# ODGIRON-v1_0-F103-0413.net
KiCad netlist of a schematic drawn in EAGLE
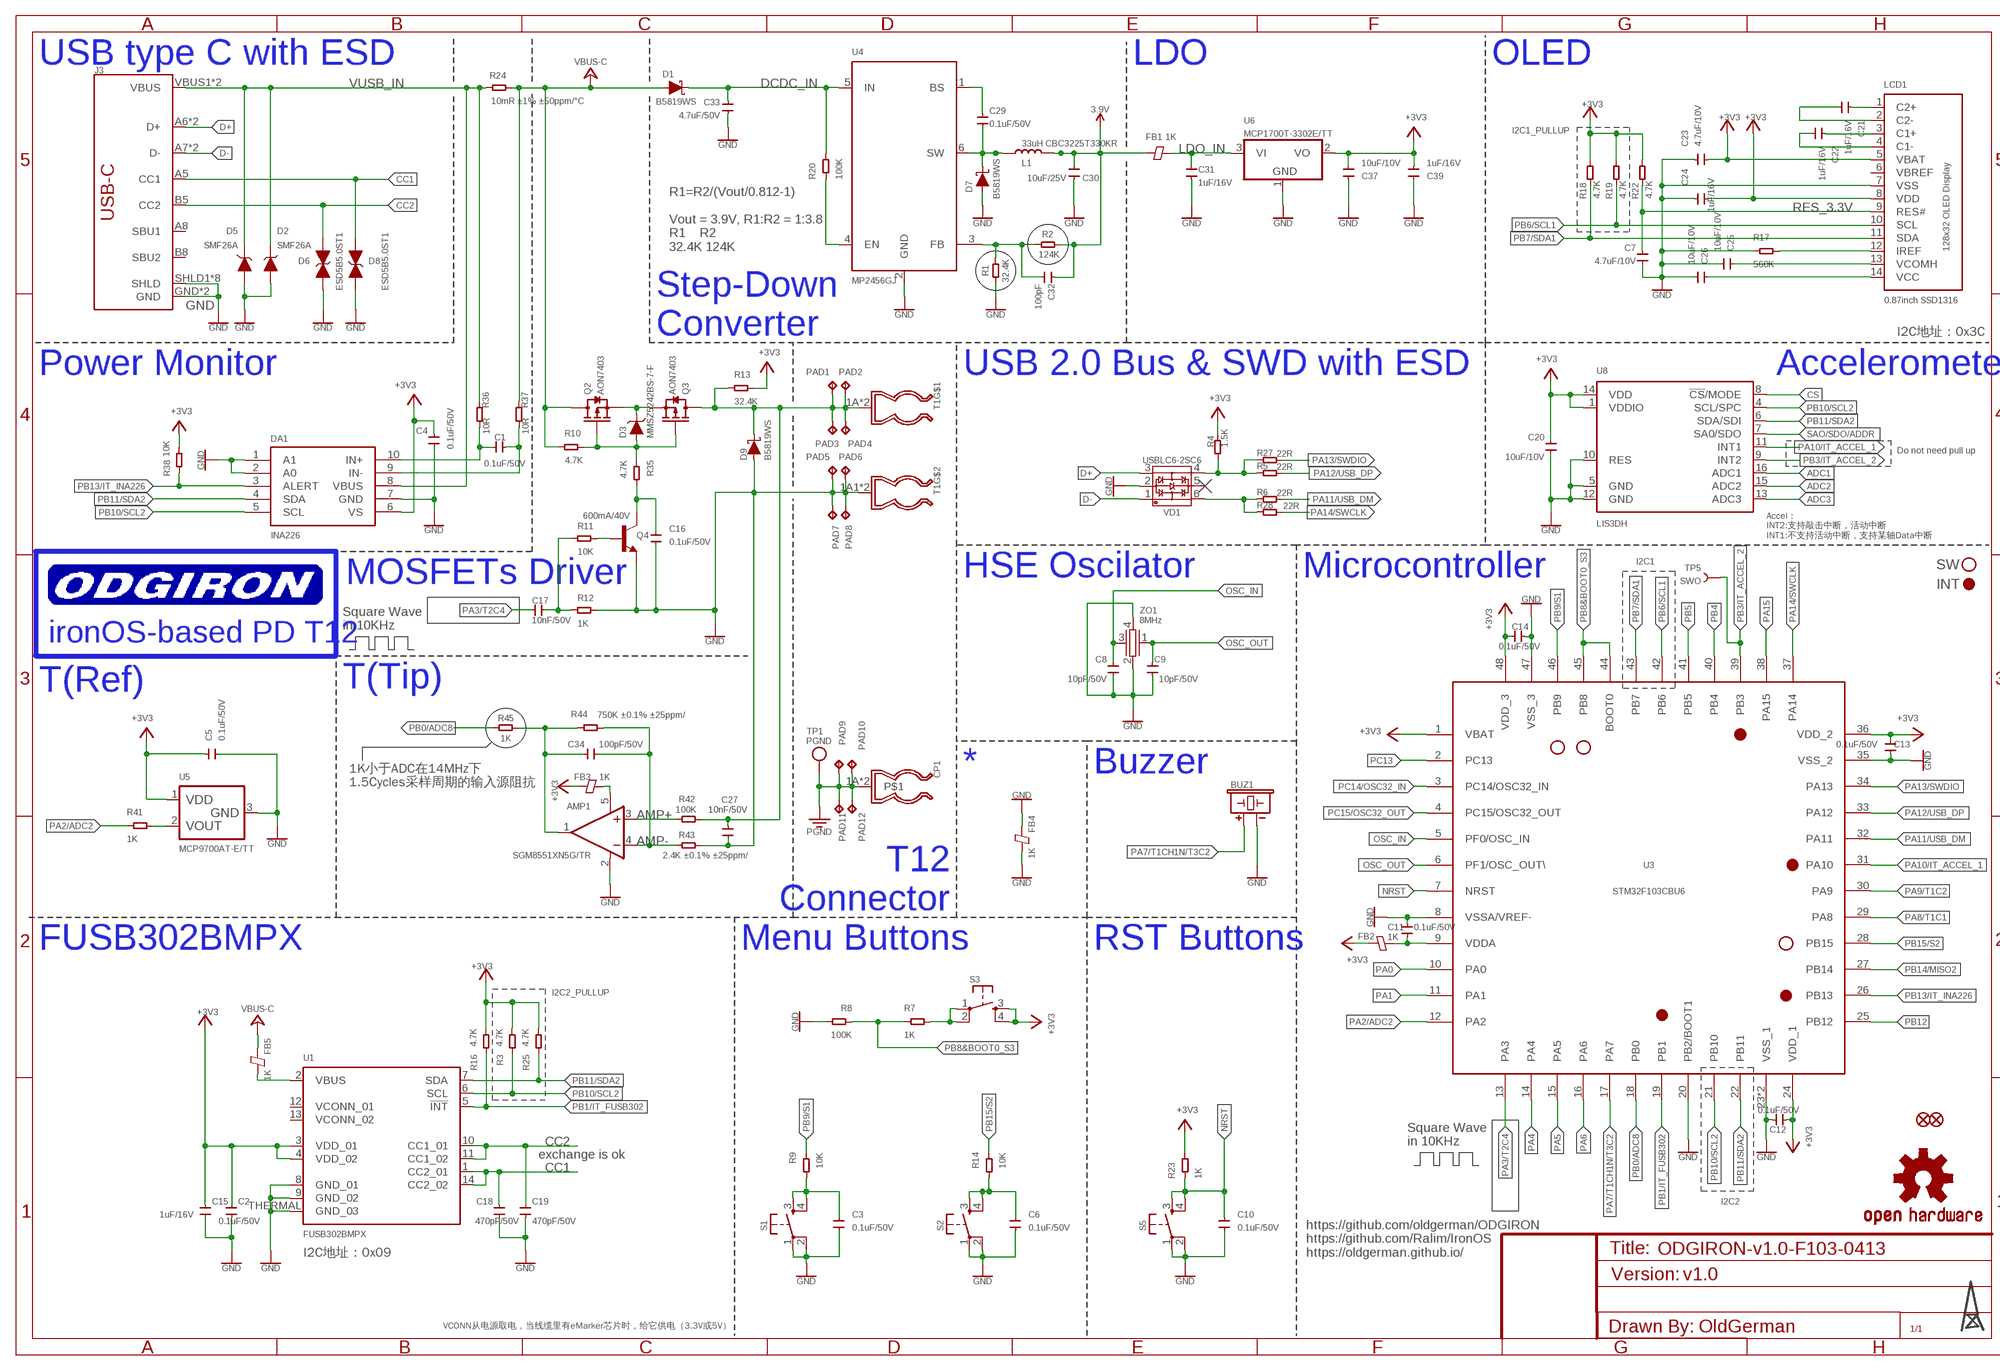
[diagram p0: schematic, sheet 1, part 1 of 2]
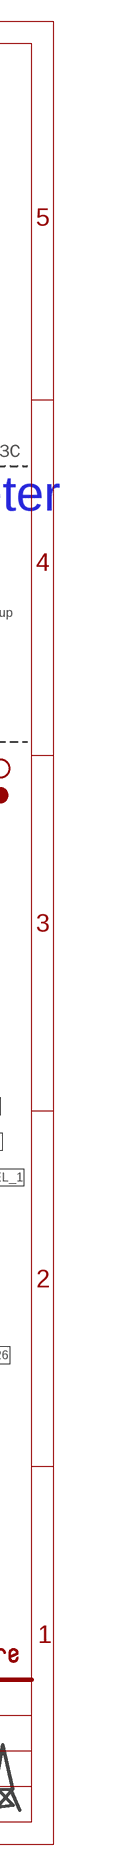
[diagram p1: schematic, sheet 1, part 2 of 2]

(export (version "E")
  (design (tool "Eeschema 10.0.6"))
  (components
    (comp (ref "AMP1")
      (value "SGM8551XN5G/TR")
      (footprint "eagle-import:SOT23-5")
      (fields (field (name "MPN") "OPA340NA/3KG4"))
      (libsource (lib "eagle-import") (part "AMP_SIMGLEN"))
    )
    (comp (ref "BUZ1")
      (value "BUZZERBUZZER_5020")
      (footprint "eagle-import:BUZZER_5020")
      (libsource (lib "eagle-import") (part "BUZZERBUZZER_5020"))
    )
    (comp (ref "C1")
      (value "0.1uF/50V")
      (footprint "eagle-import:C0603")
      (libsource (lib "eagle-import") (part "SEEED_CAP-0603"))
    )
    (comp (ref "C2")
      (value "0.1uF/50V")
      (footprint "eagle-import:C0603")
      (libsource (lib "eagle-import") (part "SEEED_CAP-0603"))
    )
    (comp (ref "C3")
      (value "0.1uF/50V")
      (footprint "eagle-import:C0603")
      (libsource (lib "eagle-import") (part "SEEED_CAP-0603"))
    )
    (comp (ref "C4")
      (value "0.1uF/50V")
      (footprint "eagle-import:C0603")
      (libsource (lib "eagle-import") (part "SEEED_CAP-0603"))
    )
    (comp (ref "C5")
      (value "0.1uF/50V")
      (footprint "eagle-import:C0603")
      (libsource (lib "eagle-import") (part "SEEED_CAP-0603"))
    )
    (comp (ref "C6")
      (value "0.1uF/50V")
      (footprint "eagle-import:C0603")
      (libsource (lib "eagle-import") (part "SEEED_CAP-0603"))
    )
    (comp (ref "C7")
      (value "4.7uF/10V")
      (footprint "eagle-import:C0603")
      (libsource (lib "eagle-import") (part "SEEED_CAP-0603"))
    )
    (comp (ref "C8")
      (value "10pF/50V")
      (footprint "eagle-import:C0603")
      (libsource (lib "eagle-import") (part "SEEED_CAP-0603"))
    )
    (comp (ref "C9")
      (value "10pF/50V")
      (footprint "eagle-import:C0603")
      (libsource (lib "eagle-import") (part "SEEED_CAP-0603"))
    )
    (comp (ref "C10")
      (value "0.1uF/50V")
      (footprint "eagle-import:C0603")
      (libsource (lib "eagle-import") (part "SEEED_CAP-0603"))
    )
    (comp (ref "C11")
      (value "0.1uF/50V")
      (footprint "eagle-import:C0603")
      (libsource (lib "eagle-import") (part "SEEED_CAP-0603"))
    )
    (comp (ref "C12")
      (value "0.1uF/50V")
      (footprint "eagle-import:C0603")
      (libsource (lib "eagle-import") (part "SEEED_CAP-0603"))
    )
    (comp (ref "C13")
      (value "0.1uF/50V")
      (footprint "eagle-import:C0603")
      (libsource (lib "eagle-import") (part "SEEED_CAP-0603"))
    )
    (comp (ref "C14")
      (value "0.1uF/50V")
      (footprint "eagle-import:C0603")
      (libsource (lib "eagle-import") (part "SEEED_CAP-0603"))
    )
    (comp (ref "C15")
      (value "1uF/16V")
      (footprint "eagle-import:C0603")
      (libsource (lib "eagle-import") (part "SEEED_CAP-0603"))
    )
    (comp (ref "C16")
      (value "0.1uF/50V")
      (footprint "eagle-import:C0603")
      (libsource (lib "eagle-import") (part "SEEED_CAP-0603"))
    )
    (comp (ref "C17")
      (value "10nF/50V")
      (footprint "eagle-import:C0603")
      (libsource (lib "eagle-import") (part "SEEED_CAP-0603"))
    )
    (comp (ref "C18")
      (value "470pF/50V")
      (footprint "eagle-import:C0603")
      (libsource (lib "eagle-import") (part "SEEED_CAP-0603"))
    )
    (comp (ref "C19")
      (value "470pF/50V")
      (footprint "eagle-import:C0603")
      (libsource (lib "eagle-import") (part "SEEED_CAP-0603"))
    )
    (comp (ref "C20")
      (value "10uF/10V")
      (footprint "eagle-import:C0603")
      (libsource (lib "eagle-import") (part "SEEED_CAP-0603"))
    )
    (comp (ref "C21")
      (value "1uF/16V")
      (footprint "eagle-import:C0603")
      (libsource (lib "eagle-import") (part "SEEED_CAP-0603"))
    )
    (comp (ref "C22")
      (value "1uF/16V")
      (footprint "eagle-import:C0603")
      (libsource (lib "eagle-import") (part "SEEED_CAP-0603"))
    )
    (comp (ref "C23")
      (value "4.7uF/10V")
      (footprint "eagle-import:C0603")
      (libsource (lib "eagle-import") (part "SEEED_CAP-0603"))
    )
    (comp (ref "C24")
      (value "1uF/16V")
      (footprint "eagle-import:C0603")
      (libsource (lib "eagle-import") (part "SEEED_CAP-0603"))
    )
    (comp (ref "C25")
      (value "10uF/10V")
      (footprint "eagle-import:C0603")
      (libsource (lib "eagle-import") (part "SEEED_CAP-0603"))
    )
    (comp (ref "C26")
      (value "10uF/10V")
      (footprint "eagle-import:C0603")
      (libsource (lib "eagle-import") (part "SEEED_CAP-0603"))
    )
    (comp (ref "C27")
      (value "10nF/50V")
      (footprint "eagle-import:C0603")
      (libsource (lib "eagle-import") (part "SEEED_CAP-0603"))
    )
    (comp (ref "C29")
      (value "0.1uF/50V")
      (footprint "eagle-import:C0603")
      (libsource (lib "eagle-import") (part "SEEED_CAP-0603"))
    )
    (comp (ref "C30")
      (value "10uF/25V")
      (footprint "eagle-import:C0805")
      (libsource (lib "eagle-import") (part "SEEED_CAP-0805"))
    )
    (comp (ref "C31")
      (value "1uF/16V")
      (footprint "eagle-import:C0603")
      (libsource (lib "eagle-import") (part "SEEED_CAP-0603"))
    )
    (comp (ref "C32")
      (value "100pF")
      (footprint "eagle-import:C0603")
      (libsource (lib "eagle-import") (part "SEEED_CAP-0603"))
    )
    (comp (ref "C33")
      (value "4.7uF/50V")
      (footprint "eagle-import:C0805")
      (libsource (lib "eagle-import") (part "SEEED_CAP-0805"))
    )
    (comp (ref "C34")
      (value "100pF/50V")
      (footprint "eagle-import:C0603")
      (libsource (lib "eagle-import") (part "SEEED_CAP-0603"))
    )
    (comp (ref "C37")
      (value "10uF/10V")
      (footprint "eagle-import:C0603")
      (libsource (lib "eagle-import") (part "SEEED_CAP-0603"))
    )
    (comp (ref "C39")
      (value "1uF/16V")
      (footprint "eagle-import:C0603")
      (libsource (lib "eagle-import") (part "SEEED_CAP-0603"))
    )
    (comp (ref "CP1")
      (value "FUSE_CLIPS_01")
      (footprint "eagle-import:FUSE_CLIPS_01")
      (libsource (lib "eagle-import") (part "FUSE_CLIPS_01"))
    )
    (comp (ref "D1")
      (value "B5819WS")
      (footprint "eagle-import:SOD-323")
      (libsource (lib "eagle-import") (part "DIODE_SCHOTTKYSOD323"))
    )
    (comp (ref "D2")
      (value "SMF26A")
      (footprint "eagle-import:SOD-123")
      (libsource (lib "eagle-import") (part "DIODE-TVS_UNIDIRECTIONALSOD-123"))
    )
    (comp (ref "D3")
      (value "MMSZ5242BS-7-F")
      (footprint "eagle-import:SOD-323")
      (libsource (lib "eagle-import") (part "DIODE_ZENERSOD-323"))
    )
    (comp (ref "D5")
      (value "SMF26A")
      (footprint "eagle-import:SOD-123")
      (libsource (lib "eagle-import") (part "DIODE-TVS_UNIDIRECTIONALSOD-123"))
    )
    (comp (ref "D6")
      (value "ESD5B5.0ST1")
      (footprint "eagle-import:SOD-523")
      (libsource (lib "eagle-import") (part "DIODE-TVS_BI−DIRECTIONALSOD-523"))
    )
    (comp (ref "D7")
      (value "B5819WS")
      (footprint "eagle-import:SOD-323")
      (libsource (lib "eagle-import") (part "DIODE_SCHOTTKYSOD323"))
    )
    (comp (ref "D8")
      (value "ESD5B5.0ST1")
      (footprint "eagle-import:SOD-523")
      (libsource (lib "eagle-import") (part "DIODE-TVS_BI−DIRECTIONALSOD-523"))
    )
    (comp (ref "D9")
      (value "B5819WS")
      (footprint "eagle-import:SOD-323")
      (libsource (lib "eagle-import") (part "DIODE_SCHOTTKYSOD323"))
    )
    (comp (ref "DA1")
      (value "INA226")
      (footprint "eagle-import:MSOP10")
      (libsource (lib "eagle-import") (part "INA226"))
    )
    (comp (ref "FB1")
      (value "1K")
      (footprint "eagle-import:F0603")
      (libsource (lib "eagle-import") (part "FERRITE-BEAD-0603"))
    )
    (comp (ref "FB2")
      (value "1K")
      (footprint "eagle-import:F0603")
      (libsource (lib "eagle-import") (part "FERRITE-BEAD-0603"))
    )
    (comp (ref "FB3")
      (value "1K")
      (footprint "eagle-import:F0603")
      (libsource (lib "eagle-import") (part "FERRITE-BEAD-0603"))
    )
    (comp (ref "FB4")
      (value "1K")
      (footprint "eagle-import:F0603")
      (libsource (lib "eagle-import") (part "FERRITE-BEAD-0603"))
    )
    (comp (ref "FB5")
      (value "1K")
      (footprint "eagle-import:F0603")
      (libsource (lib "eagle-import") (part "FERRITE-BEAD-0603"))
    )
    (comp (ref "FID1")
      (value "FIDUCIAL")
      (footprint "eagle-import:FIDUCIAL_1MM")
      (libsource (lib "eagle-import") (part "FIDUCIAL"))
    )
    (comp (ref "FID2")
      (value "FIDUCIAL")
      (footprint "eagle-import:FIDUCIAL_1MM")
      (libsource (lib "eagle-import") (part "FIDUCIAL"))
    )
    (comp (ref "J3")
      (value "USB_C_LONG-SYMBOL2-LAYER")
      (footprint "eagle-import:USB-C-16P")
      (libsource (lib "eagle-import") (part "USB_C_LONG-SYMBOL2-LAYER"))
    )
    (comp (ref "L1")
      (value "33uH CBC3225T330KR")
      (footprint "eagle-import:SMD,3.2X2.5X2.5MM")
      (libsource (lib "eagle-import") (part "INDUCTOR3225"))
    )
    (comp (ref "LCD1")
      (value "0.87inch SSD1316")
      (footprint "eagle-import:0.87INCH_128X32_OLED_SSD1306")
      (libsource (lib "eagle-import") (part "0.87INCH_OLED_128X32_SSD1306"))
    )
    (comp (ref "LOGO1")
      (value "OSHW-LOGONO_SILK")
      (footprint "eagle-import:DUMMY")
      (libsource (lib "eagle-import") (part "OSHW-LOGONO_SILK"))
    )
    (comp (ref "PAD1")
      (value "PADTP16SQ")
      (footprint "eagle-import:TP16SQ")
      (libsource (lib "eagle-import") (part "PADTP16SQ"))
    )
    (comp (ref "PAD2")
      (value "PADTP16SQ")
      (footprint "eagle-import:TP16SQ")
      (libsource (lib "eagle-import") (part "PADTP16SQ"))
    )
    (comp (ref "PAD3")
      (value "PADTP16SQ")
      (footprint "eagle-import:TP16SQ")
      (libsource (lib "eagle-import") (part "PADTP16SQ"))
    )
    (comp (ref "PAD4")
      (value "PADTP16SQ")
      (footprint "eagle-import:TP16SQ")
      (libsource (lib "eagle-import") (part "PADTP16SQ"))
    )
    (comp (ref "PAD5")
      (value "PADTP16SQ")
      (footprint "eagle-import:TP16SQ")
      (libsource (lib "eagle-import") (part "PADTP16SQ"))
    )
    (comp (ref "PAD6")
      (value "PADTP16SQ")
      (footprint "eagle-import:TP16SQ")
      (libsource (lib "eagle-import") (part "PADTP16SQ"))
    )
    (comp (ref "PAD7")
      (value "PADTP16SQ")
      (footprint "eagle-import:TP16SQ")
      (libsource (lib "eagle-import") (part "PADTP16SQ"))
    )
    (comp (ref "PAD8")
      (value "PADTP16SQ")
      (footprint "eagle-import:TP16SQ")
      (libsource (lib "eagle-import") (part "PADTP16SQ"))
    )
    (comp (ref "PAD9")
      (value "PADTP16SQ")
      (footprint "eagle-import:TP16SQ")
      (libsource (lib "eagle-import") (part "PADTP16SQ"))
    )
    (comp (ref "PAD10")
      (value "PADTP16SQ")
      (footprint "eagle-import:TP16SQ")
      (libsource (lib "eagle-import") (part "PADTP16SQ"))
    )
    (comp (ref "PAD11")
      (value "PADTP16SQ")
      (footprint "eagle-import:TP16SQ")
      (libsource (lib "eagle-import") (part "PADTP16SQ"))
    )
    (comp (ref "PAD12")
      (value "PADTP16SQ")
      (footprint "eagle-import:TP16SQ")
      (libsource (lib "eagle-import") (part "PADTP16SQ"))
    )
    (comp (ref "Q2")
      (value "AON7403")
      (footprint "eagle-import:DFN8P-0.65-3X3X0.8MM")
      (libsource (lib "eagle-import") (part "MOSFET-P-AON7403"))
    )
    (comp (ref "Q3")
      (value "AON7403")
      (footprint "eagle-import:DFN8P-0.65-3X3X0.8MM")
      (libsource (lib "eagle-import") (part "MOSFET-P-AON7403"))
    )
    (comp (ref "Q4")
      (value "600mA/40V")
      (footprint "eagle-import:SOT23-3")
      (libsource (lib "eagle-import") (part "TRANS_NPN-MMBT2222AL"))
    )
    (comp (ref "R1")
      (value "32.4K")
      (footprint "eagle-import:R0603")
      (libsource (lib "eagle-import") (part "SEEED_RES-0603"))
    )
    (comp (ref "R2")
      (value "124K")
      (footprint "eagle-import:R0603")
      (libsource (lib "eagle-import") (part "SEEED_RES-0603"))
    )
    (comp (ref "R3")
      (value "4.7K")
      (footprint "eagle-import:R0603")
      (libsource (lib "eagle-import") (part "SEEED_RES-0603"))
    )
    (comp (ref "R4")
      (value "1.5K")
      (footprint "eagle-import:R0603")
      (libsource (lib "eagle-import") (part "SEEED_RES-0603"))
    )
    (comp (ref "R5")
      (value "22R")
      (footprint "eagle-import:R0603")
      (libsource (lib "eagle-import") (part "SEEED_RES-0603"))
    )
    (comp (ref "R6")
      (value "22R")
      (footprint "eagle-import:R0603")
      (libsource (lib "eagle-import") (part "SEEED_RES-0603"))
    )
    (comp (ref "R7")
      (value "1K")
      (footprint "eagle-import:R0603")
      (libsource (lib "eagle-import") (part "SEEED_RES-0603"))
    )
    (comp (ref "R8")
      (value "100K")
      (footprint "eagle-import:R0603")
      (libsource (lib "eagle-import") (part "SEEED_RES-0603"))
    )
    (comp (ref "R9")
      (value "10K")
      (footprint "eagle-import:R0603")
      (libsource (lib "eagle-import") (part "SEEED_RES-0603"))
    )
    (comp (ref "R10")
      (value "4.7K")
      (footprint "eagle-import:R0603")
      (libsource (lib "eagle-import") (part "SEEED_RES-0603"))
    )
    (comp (ref "R11")
      (value "10K")
      (footprint "eagle-import:R0603")
      (libsource (lib "eagle-import") (part "SEEED_RES-0603"))
    )
    (comp (ref "R12")
      (value "1K")
      (footprint "eagle-import:R0603")
      (libsource (lib "eagle-import") (part "SEEED_RES-0603"))
    )
    (comp (ref "R13")
      (value "32.4K")
      (footprint "eagle-import:R0603")
      (libsource (lib "eagle-import") (part "SEEED_RES-0603"))
    )
    (comp (ref "R14")
      (value "10K")
      (footprint "eagle-import:R0603")
      (libsource (lib "eagle-import") (part "SEEED_RES-0603"))
    )
    (comp (ref "R16")
      (value "4.7K")
      (footprint "eagle-import:R0603")
      (libsource (lib "eagle-import") (part "SEEED_RES-0603"))
    )
    (comp (ref "R17")
      (value "560K")
      (footprint "eagle-import:R0603")
      (libsource (lib "eagle-import") (part "SEEED_RES-0603"))
    )
    (comp (ref "R18")
      (value "4.7K")
      (footprint "eagle-import:R0603")
      (libsource (lib "eagle-import") (part "SEEED_RES-0603"))
    )
    (comp (ref "R19")
      (value "4.7K")
      (footprint "eagle-import:R0603")
      (libsource (lib "eagle-import") (part "SEEED_RES-0603"))
    )
    (comp (ref "R20")
      (value "100K")
      (footprint "eagle-import:R0603")
      (libsource (lib "eagle-import") (part "SEEED_RES-0603"))
    )
    (comp (ref "R22")
      (value "4.7K")
      (footprint "eagle-import:R0603")
      (libsource (lib "eagle-import") (part "SEEED_RES-0603"))
    )
    (comp (ref "R23")
      (value "1K")
      (footprint "eagle-import:R0603")
      (libsource (lib "eagle-import") (part "SEEED_RES-0603"))
    )
    (comp (ref "R24")
      (value "10mR ±1% ±50ppm/°C")
      (footprint "eagle-import:R1206")
      (libsource (lib "eagle-import") (part "SEEED_RES-1206"))
    )
    (comp (ref "R25")
      (value "4.7K")
      (footprint "eagle-import:R0603")
      (libsource (lib "eagle-import") (part "SEEED_RES-0603"))
    )
    (comp (ref "R27")
      (value "22R")
      (footprint "eagle-import:R0603")
      (libsource (lib "eagle-import") (part "SEEED_RES-0603"))
    )
    (comp (ref "R28")
      (value "22R")
      (footprint "eagle-import:R0603")
      (libsource (lib "eagle-import") (part "SEEED_RES-0603"))
    )
    (comp (ref "R35")
      (value "4.7K")
      (footprint "eagle-import:R0603")
      (libsource (lib "eagle-import") (part "SEEED_RES-0603"))
    )
    (comp (ref "R36")
      (value "10R")
      (footprint "eagle-import:R0603")
      (libsource (lib "eagle-import") (part "SEEED_RES-0603"))
    )
    (comp (ref "R37")
      (value "10R")
      (footprint "eagle-import:R0603")
      (libsource (lib "eagle-import") (part "SEEED_RES-0603"))
    )
    (comp (ref "R38")
      (value "10K")
      (footprint "eagle-import:R0603")
      (libsource (lib "eagle-import") (part "SEEED_RES-0603"))
    )
    (comp (ref "R41")
      (value "1K")
      (footprint "eagle-import:R0603")
      (libsource (lib "eagle-import") (part "SEEED_RES-0603"))
    )
    (comp (ref "R42")
      (value "100K")
      (footprint "eagle-import:R0603")
      (libsource (lib "eagle-import") (part "SEEED_RES-0603"))
    )
    (comp (ref "R43")
      (value "2.4K ±0.1% ±25ppm/℃")
      (footprint "eagle-import:R0603")
      (libsource (lib "eagle-import") (part "SEEED_RES-0603"))
    )
    (comp (ref "R44")
      (value "750K ±0.1% ±25ppm/℃")
      (footprint "eagle-import:R0603")
      (libsource (lib "eagle-import") (part "SEEED_RES-0603"))
    )
    (comp (ref "R45")
      (value "1K")
      (footprint "eagle-import:R0603")
      (libsource (lib "eagle-import") (part "SEEED_RES-0603"))
    )
    (comp (ref "S1")
      (value "TAC_SWITCHSMD")
      (footprint "eagle-import:TACTILE_SWITCH_SMD")
      (libsource (lib "eagle-import") (part "TAC_SWITCHSMD"))
    )
    (comp (ref "S2")
      (value "TAC_SWITCHSMD")
      (footprint "eagle-import:TACTILE_SWITCH_SMD")
      (libsource (lib "eagle-import") (part "TAC_SWITCHSMD"))
    )
    (comp (ref "S3")
      (value "TAC_SWITCHSMD")
      (footprint "eagle-import:TACTILE_SWITCH_SMD")
      (libsource (lib "eagle-import") (part "TAC_SWITCHSMD"))
    )
    (comp (ref "S5")
      (value "TAC_SWITCHSMD")
      (footprint "eagle-import:TACTILE_SWITCH_SMD")
      (libsource (lib "eagle-import") (part "untitled_TAC_SWITCHSMD"))
    )
    (comp (ref "T1")
      (value "HAKKO_T12_K-TYPE_WITH_FUSE_CLIPS_X2")
      (footprint "eagle-import:HAKKO_T12_K-TYPE_WITH_FUSE_CLIPS_X2")
      (libsource (lib "eagle-import") (part "HAKKO_T12_K-TYPE_WITH_FUSE_CLIPS_X2"))
    )
    (comp (ref "TP1")
      (value "PGND")
      (footprint "eagle-import:TESTPOINT_ROUND_2MM")
      (libsource (lib "eagle-import") (part "TESTPOINTROUND2MM"))
    )
    (comp (ref "TP5")
      (value "SWO")
      (footprint "eagle-import:PAD.03X.03")
      (libsource (lib "eagle-import") (part "TEST-POINT3"))
    )
    (comp (ref "U1")
      (value "FUSB302BMPX")
      (footprint "eagle-import:QFN14-2.5X2.5MM")
      (libsource (lib "eagle-import") (part "FUSB302"))
    )
    (comp (ref "U3")
      (value "STM32F103CBU6")
      (footprint "eagle-import:QFN48_7X7MM_0.5MM")
      (libsource (lib "eagle-import") (part "STM32F1_QFN48"))
    )
    (comp (ref "U4")
      (value "MP2456GJ")
      (footprint "eagle-import:SOT23-6")
      (libsource (lib "eagle-import") (part "MP2456"))
    )
    (comp (ref "U5")
      (value "MCP9700AT-E/TT")
      (footprint "eagle-import:SOT23-3@1")
      (libsource (lib "eagle-import") (part "MCP9700"))
    )
    (comp (ref "U6")
      (value "MCP1700T-3302E/TT")
      (footprint "eagle-import:SOT23-3")
      (libsource (lib "eagle-import") (part "MCP1700"))
    )
    (comp (ref "U8")
      (value "LIS3DH")
      (footprint "eagle-import:LGA-16-3X3")
      (libsource (lib "eagle-import") (part "LIS3DH"))
    )
    (comp (ref "VD1")
      (value "USBLC6-2SC6")
      (footprint "eagle-import:SOT23-6")
      (libsource (lib "eagle-import") (part "USBLC6-2SOT23-6"))
    )
    (comp (ref "ZO1")
      (value "8MHz")
      (footprint "eagle-import:3.2X2.5_KX-7")
      (libsource (lib "eagle-import") (part "3225_CRYSTALL"))
    )
  )
  (nets
    (net (code "1") (name "+3V3") (class "Default")
      (node (ref "C12") (pin "2") (pinfunction "P$2_2") (pintype "passive"))
      (node (ref "C13") (pin "2") (pinfunction "P$2_2") (pintype "passive"))
      (node (ref "C14") (pin "2") (pinfunction "P$2_2") (pintype "passive"))
      (node (ref "C15") (pin "1") (pinfunction "P$1_1") (pintype "passive"))
      (node (ref "C2") (pin "1") (pinfunction "P$1_1") (pintype "passive"))
      (node (ref "C20") (pin "2") (pinfunction "P$2_2") (pintype "passive"))
      (node (ref "C23") (pin "2") (pinfunction "P$2_2") (pintype "passive"))
      (node (ref "C24") (pin "2") (pinfunction "P$2_2") (pintype "passive"))
      (node (ref "C37") (pin "2") (pinfunction "P$2_2") (pintype "passive"))
      (node (ref "C39") (pin "2") (pinfunction "P$2_2") (pintype "passive"))
      (node (ref "C4") (pin "1") (pinfunction "P$1_1") (pintype "passive"))
      (node (ref "C5") (pin "1") (pinfunction "P$1_1") (pintype "passive"))
      (node (ref "DA1") (pin "6") (pinfunction "VS_6") (pintype "bidirectional"))
      (node (ref "FB2") (pin "2") (pinfunction "2_2") (pintype "bidirectional"))
      (node (ref "FB3") (pin "2") (pinfunction "2_2") (pintype "bidirectional"))
      (node (ref "LCD1") (pin "5") (pinfunction "VBAT_5") (pintype "power_in"))
      (node (ref "LCD1") (pin "8") (pinfunction "VDD_8") (pintype "power_in"))
      (node (ref "R13") (pin "2") (pinfunction "2_2") (pintype "passive"))
      (node (ref "R16") (pin "1") (pinfunction "1_1") (pintype "passive"))
      (node (ref "R18") (pin "2") (pinfunction "2_2") (pintype "passive"))
      (node (ref "R19") (pin "2") (pinfunction "2_2") (pintype "passive"))
      (node (ref "R22") (pin "2") (pinfunction "2_2") (pintype "passive"))
      (node (ref "R23") (pin "2") (pinfunction "2_2") (pintype "passive"))
      (node (ref "R25") (pin "1") (pinfunction "1_1") (pintype "passive"))
      (node (ref "R3") (pin "1") (pinfunction "1_1") (pintype "passive"))
      (node (ref "R38") (pin "1") (pinfunction "1_1") (pintype "passive"))
      (node (ref "R4") (pin "2") (pinfunction "2_2") (pintype "passive"))
      (node (ref "S3") (pin "3") (pinfunction "3_3") (pintype "passive"))
      (node (ref "S3") (pin "4") (pinfunction "4_4") (pintype "passive"))
      (node (ref "U1") (pin "3") (pinfunction "VDD_01_3") (pintype "bidirectional"))
      (node (ref "U1") (pin "4") (pinfunction "VDD_02_4") (pintype "bidirectional"))
      (node (ref "U3") (pin "1") (pinfunction "VBAT_1") (pintype "bidirectional"))
      (node (ref "U3") (pin "24") (pinfunction "VDD_1_24") (pintype "bidirectional"))
      (node (ref "U3") (pin "36") (pinfunction "VDD_2_36") (pintype "bidirectional"))
      (node (ref "U3") (pin "48") (pinfunction "VDD_3_48") (pintype "bidirectional"))
      (node (ref "U5") (pin "1") (pinfunction "VDD_1") (pintype "input"))
      (node (ref "U6") (pin "2") (pinfunction "VO_2") (pintype "passive"))
      (node (ref "U8") (pin "1") (pinfunction "VDDIO_1") (pintype "bidirectional"))
      (node (ref "U8") (pin "14") (pinfunction "VDD_14") (pintype "bidirectional"))
    )
    (net (code "2") (name "/AMP+") (class "Default")
      (node (ref "AMP1") (pin "3") (pinfunction "+IN_3") (pintype "input"))
      (node (ref "R42") (pin "1") (pinfunction "1_1") (pintype "passive"))
    )
    (net (code "3") (name "/AMP-") (class "Default")
      (node (ref "AMP1") (pin "4") (pinfunction "-IN_4") (pintype "input"))
      (node (ref "C34") (pin "2") (pinfunction "P$2_2") (pintype "passive"))
      (node (ref "R43") (pin "1") (pinfunction "1_1") (pintype "passive"))
      (node (ref "R44") (pin "2") (pinfunction "2_2") (pintype "passive"))
    )
    (net (code "4") (name "/DCDC_IN") (class "Default")
      (node (ref "C33") (pin "1") (pinfunction "P$1_1") (pintype "passive"))
      (node (ref "D1") (pin "C") (pinfunction "C_C") (pintype "passive"))
      (node (ref "R20") (pin "2") (pinfunction "2_2") (pintype "passive"))
      (node (ref "U4") (pin "5") (pinfunction "IN_5") (pintype "bidirectional"))
    )
    (net (code "5") (name "/LDO_IN") (class "Default")
      (node (ref "C31") (pin "2") (pinfunction "P$2_2") (pintype "passive"))
      (node (ref "FB1") (pin "2") (pinfunction "2_2") (pintype "bidirectional"))
      (node (ref "U6") (pin "3") (pinfunction "VI_3") (pintype "input"))
    )
    (net (code "6") (name "/RES_3.3V") (class "Default")
      (node (ref "C7") (pin "1") (pinfunction "P$1_1") (pintype "passive"))
      (node (ref "LCD1") (pin "9") (pinfunction "RES#_9") (pintype "bidirectional"))
      (node (ref "R22") (pin "1") (pinfunction "1_1") (pintype "passive"))
    )
    (net (code "7") (name "/VBREF") (class "Default")
      (node (ref "LCD1") (pin "6") (pinfunction "VBREF_6") (pintype "power_in"))
    )
    (net (code "8") (name "/VUSB_IN") (class "Default")
      (node (ref "D2") (pin "C") (pinfunction "K_C") (pintype "passive"))
      (node (ref "D5") (pin "C") (pinfunction "K_C") (pintype "passive"))
      (node (ref "DA1") (pin "8") (pinfunction "VBUS_8") (pintype "bidirectional"))
      (node (ref "J3") (pin "VBUS1") (pinfunction "VBUS_VBUS1") (pintype "bidirectional"))
      (node (ref "J3") (pin "VBUS2") (pinfunction "VBUS_VBUS2") (pintype "bidirectional"))
      (node (ref "R24") (pin "2") (pinfunction "2_2") (pintype "passive"))
      (node (ref "R36") (pin "2") (pinfunction "2_2") (pintype "passive"))
    )
    (net (code "9") (name "3.9V") (class "Default")
      (node (ref "C30") (pin "1") (pinfunction "P$1_1") (pintype "passive"))
      (node (ref "C32") (pin "1") (pinfunction "P$1_1") (pintype "passive"))
      (node (ref "FB1") (pin "1") (pinfunction "1_1") (pintype "bidirectional"))
      (node (ref "L1") (pin "2") (pinfunction "2_2") (pintype "passive"))
      (node (ref "R2") (pin "1") (pinfunction "1_1") (pintype "passive"))
    )
    (net (code "10") (name "ADC1") (class "Default")
      (node (ref "U8") (pin "16") (pinfunction "ADC1_16") (pintype "bidirectional"))
    )
    (net (code "11") (name "ADC2") (class "Default")
      (node (ref "U8") (pin "15") (pinfunction "ADC2_15") (pintype "bidirectional"))
    )
    (net (code "12") (name "ADC3") (class "Default")
      (node (ref "U8") (pin "13") (pinfunction "ADC3_13") (pintype "bidirectional"))
    )
    (net (code "13") (name "CC1") (class "Default")
      (node (ref "C18") (pin "1") (pinfunction "P$1_1") (pintype "passive"))
      (node (ref "D8") (pin "K") (pinfunction "C_K") (pintype "passive"))
      (node (ref "J3") (pin "A5") (pinfunction "CC1_A5") (pintype "bidirectional"))
      (node (ref "U1") (pin "1") (pinfunction "CC2_01_1") (pintype "bidirectional"))
      (node (ref "U1") (pin "14") (pinfunction "CC2_02_14") (pintype "bidirectional"))
    )
    (net (code "14") (name "CC2") (class "Default")
      (node (ref "C19") (pin "1") (pinfunction "P$1_1") (pintype "passive"))
      (node (ref "D6") (pin "K") (pinfunction "C_K") (pintype "passive"))
      (node (ref "J3") (pin "B5") (pinfunction "CC2_B5") (pintype "bidirectional"))
      (node (ref "U1") (pin "10") (pinfunction "CC1_01_10") (pintype "bidirectional"))
      (node (ref "U1") (pin "11") (pinfunction "CC1_02_11") (pintype "bidirectional"))
    )
    (net (code "15") (name "CS") (class "Default")
      (node (ref "U8") (pin "8") (pinfunction "~{CS}/MODE_8") (pintype "bidirectional"))
    )
    (net (code "16") (name "D+") (class "Default")
      (node (ref "J3") (pin "A6") (pinfunction "D+_A6") (pintype "bidirectional"))
      (node (ref "J3") (pin "B6") (pinfunction "D+_B6") (pintype "bidirectional"))
      (node (ref "VD1") (pin "3") (pinfunction "P$3_3") (pintype "bidirectional"))
    )
    (net (code "17") (name "D-") (class "Default")
      (node (ref "J3") (pin "A7") (pinfunction "D-_A7") (pintype "bidirectional"))
      (node (ref "J3") (pin "B7") (pinfunction "D-_B7") (pintype "bidirectional"))
      (node (ref "VD1") (pin "1") (pinfunction "P$1_1") (pintype "bidirectional"))
    )
    (net (code "18") (name "GND") (class "Default")
      (node (ref "AMP1") (pin "2") (pinfunction "V-_2") (pintype "power_in"))
      (node (ref "BUZ1") (pin "-") (pinfunction "LEAD-_-") (pintype "passive"))
      (node (ref "C10") (pin "2") (pinfunction "P$2_2") (pintype "passive"))
      (node (ref "C11") (pin "1") (pinfunction "P$1_1") (pintype "passive"))
      (node (ref "C12") (pin "1") (pinfunction "P$1_1") (pintype "passive"))
      (node (ref "C13") (pin "1") (pinfunction "P$1_1") (pintype "passive"))
      (node (ref "C14") (pin "1") (pinfunction "P$1_1") (pintype "passive"))
      (node (ref "C15") (pin "2") (pinfunction "P$2_2") (pintype "passive"))
      (node (ref "C16") (pin "1") (pinfunction "P$1_1") (pintype "passive"))
      (node (ref "C18") (pin "2") (pinfunction "P$2_2") (pintype "passive"))
      (node (ref "C19") (pin "2") (pinfunction "P$2_2") (pintype "passive"))
      (node (ref "C2") (pin "2") (pinfunction "P$2_2") (pintype "passive"))
      (node (ref "C20") (pin "1") (pinfunction "P$1_1") (pintype "passive"))
      (node (ref "C23") (pin "1") (pinfunction "P$1_1") (pintype "passive"))
      (node (ref "C24") (pin "1") (pinfunction "P$1_1") (pintype "passive"))
      (node (ref "C25") (pin "2") (pinfunction "P$2_2") (pintype "passive"))
      (node (ref "C26") (pin "2") (pinfunction "P$2_2") (pintype "passive"))
      (node (ref "C27") (pin "2") (pinfunction "P$2_2") (pintype "passive"))
      (node (ref "C3") (pin "2") (pinfunction "P$2_2") (pintype "passive"))
      (node (ref "C30") (pin "2") (pinfunction "P$2_2") (pintype "passive"))
      (node (ref "C31") (pin "1") (pinfunction "P$1_1") (pintype "passive"))
      (node (ref "C33") (pin "2") (pinfunction "P$2_2") (pintype "passive"))
      (node (ref "C37") (pin "1") (pinfunction "P$1_1") (pintype "passive"))
      (node (ref "C39") (pin "1") (pinfunction "P$1_1") (pintype "passive"))
      (node (ref "C4") (pin "2") (pinfunction "P$2_2") (pintype "passive"))
      (node (ref "C5") (pin "2") (pinfunction "P$2_2") (pintype "passive"))
      (node (ref "C6") (pin "2") (pinfunction "P$2_2") (pintype "passive"))
      (node (ref "C7") (pin "2") (pinfunction "P$2_2") (pintype "passive"))
      (node (ref "C8") (pin "1") (pinfunction "P$1_1") (pintype "passive"))
      (node (ref "C9") (pin "1") (pinfunction "P$1_1") (pintype "passive"))
      (node (ref "D2") (pin "A") (pinfunction "A_A") (pintype "passive"))
      (node (ref "D5") (pin "A") (pinfunction "A_A") (pintype "passive"))
      (node (ref "D6") (pin "A") (pinfunction "A_A") (pintype "passive"))
      (node (ref "D7") (pin "A") (pinfunction "A_A") (pintype "passive"))
      (node (ref "D8") (pin "A") (pinfunction "A_A") (pintype "passive"))
      (node (ref "D9") (pin "A") (pinfunction "A_A") (pintype "passive"))
      (node (ref "DA1") (pin "1") (pinfunction "A1_1") (pintype "bidirectional"))
      (node (ref "DA1") (pin "2") (pinfunction "A0_2") (pintype "bidirectional"))
      (node (ref "DA1") (pin "7") (pinfunction "GND_7") (pintype "bidirectional"))
      (node (ref "FB4") (pin "1") (pinfunction "1_1") (pintype "bidirectional"))
      (node (ref "FB4") (pin "2") (pinfunction "2_2") (pintype "bidirectional"))
      (node (ref "J3") (pin "GND") (pinfunction "GND_GND") (pintype "bidirectional"))
      (node (ref "J3") (pin "GND2") (pinfunction "GND_GND2") (pintype "bidirectional"))
      (node (ref "J3") (pin "SHLD1") (pinfunction "SHLD_SHLD1") (pintype "bidirectional"))
      (node (ref "J3") (pin "SHLD2") (pinfunction "SHLD_SHLD2") (pintype "bidirectional"))
      (node (ref "J3") (pin "SHLD3") (pinfunction "SHLD_SHLD3") (pintype "bidirectional"))
      (node (ref "J3") (pin "SHLD4") (pinfunction "SHLD_SHLD4") (pintype "bidirectional"))
      (node (ref "J3") (pin "SHLD5") (pinfunction "SHLD_SHLD5") (pintype "bidirectional"))
      (node (ref "J3") (pin "SHLD6") (pinfunction "SHLD_SHLD6") (pintype "bidirectional"))
      (node (ref "J3") (pin "SHLD7") (pinfunction "SHLD_SHLD7") (pintype "bidirectional"))
      (node (ref "J3") (pin "SHLD8") (pinfunction "SHLD_SHLD8") (pintype "bidirectional"))
      (node (ref "LCD1") (pin "7") (pinfunction "VSS_7") (pintype "power_in"))
      (node (ref "PAD5") (pin "TP") (pinfunction "TP_TP") (pintype "input"))
      (node (ref "PAD6") (pin "TP") (pinfunction "TP_TP") (pintype "input"))
      (node (ref "PAD7") (pin "TP") (pinfunction "TP_TP") (pintype "input"))
      (node (ref "PAD8") (pin "TP") (pinfunction "TP_TP") (pintype "input"))
      (node (ref "Q4") (pin "2") (pinfunction "E_2") (pintype "passive"))
      (node (ref "R1") (pin "1") (pinfunction "1_1") (pintype "passive"))
      (node (ref "R12") (pin "1") (pinfunction "1_1") (pintype "passive"))
      (node (ref "R17") (pin "1") (pinfunction "1_1") (pintype "passive"))
      (node (ref "R43") (pin "2") (pinfunction "2_2") (pintype "passive"))
      (node (ref "R8") (pin "2") (pinfunction "2_2") (pintype "passive"))
      (node (ref "S1") (pin "1") (pinfunction "1_1") (pintype "passive"))
      (node (ref "S1") (pin "2") (pinfunction "2_2") (pintype "passive"))
      (node (ref "S2") (pin "1") (pinfunction "1_1") (pintype "passive"))
      (node (ref "S2") (pin "2") (pinfunction "2_2") (pintype "passive"))
      (node (ref "S5") (pin "1") (pinfunction "1_1") (pintype "passive"))
      (node (ref "S5") (pin "2") (pinfunction "2_2") (pintype "passive"))
      (node (ref "T1") (pin "1A1") (pinfunction "P$1_1A1") (pintype "bidirectional"))
      (node (ref "T1") (pin "1B1") (pinfunction "P$1_1B1") (pintype "bidirectional"))
      (node (ref "U1") (pin "8") (pinfunction "GND_01_8") (pintype "bidirectional"))
      (node (ref "U1") (pin "9") (pinfunction "GND_02_9") (pintype "bidirectional"))
      (node (ref "U1") (pin "THERMAL") (pinfunction "GND_03_THERMAL") (pintype "bidirectional"))
      (node (ref "U3") (pin "20") (pinfunction "PB2/BOOT1_20") (pintype "bidirectional"))
      (node (ref "U3") (pin "23") (pinfunction "VSS_1_23") (pintype "bidirectional"))
      (node (ref "U3") (pin "35") (pinfunction "VSS_2_35") (pintype "bidirectional"))
      (node (ref "U3") (pin "47") (pinfunction "VSS_3_47") (pintype "bidirectional"))
      (node (ref "U3") (pin "8") (pinfunction "VSSA/VREF-_8") (pintype "bidirectional"))
      (node (ref "U3") (pin "P$1") (pinfunction "VSS_1_P$1") (pintype "bidirectional"))
      (node (ref "U4") (pin "2") (pinfunction "GND_2") (pintype "bidirectional"))
      (node (ref "U5") (pin "3") (pinfunction "GND_3") (pintype "passive"))
      (node (ref "U6") (pin "1") (pinfunction "GND_1") (pintype "passive"))
      (node (ref "U8") (pin "10") (pinfunction "RES_10") (pintype "bidirectional"))
      (node (ref "U8") (pin "12") (pinfunction "GND_12") (pintype "bidirectional"))
      (node (ref "U8") (pin "5") (pinfunction "GND_5") (pintype "bidirectional"))
      (node (ref "VD1") (pin "2") (pinfunction "P$2_2") (pintype "bidirectional"))
      (node (ref "ZO1") (pin "2") (pinfunction "P$3_2") (pintype "power_in"))
      (node (ref "ZO1") (pin "4") (pinfunction "P$4_4") (pintype "power_in"))
    )
    (net (code "19") (name "NRST") (class "Default")
      (node (ref "C10") (pin "1") (pinfunction "P$1_1") (pintype "passive"))
      (node (ref "R23") (pin "1") (pinfunction "1_1") (pintype "passive"))
      (node (ref "S5") (pin "3") (pinfunction "3_3") (pintype "passive"))
      (node (ref "S5") (pin "4") (pinfunction "4_4") (pintype "passive"))
      (node (ref "U3") (pin "7") (pinfunction "NRST_7") (pintype "bidirectional"))
    )
    (net (code "20") (name "Net-(AMP1-OUT)") (class "Default")
      (node (ref "AMP1") (pin "1") (pinfunction "OUT_1") (pintype "output"))
      (node (ref "C34") (pin "1") (pinfunction "P$1_1") (pintype "passive"))
      (node (ref "R44") (pin "1") (pinfunction "1_1") (pintype "passive"))
      (node (ref "R45") (pin "2") (pinfunction "2_2") (pintype "passive"))
    )
    (net (code "21") (name "Net-(AMP1-V+)") (class "Default")
      (node (ref "AMP1") (pin "5") (pinfunction "V+_5") (pintype "power_in"))
      (node (ref "FB3") (pin "1") (pinfunction "1_1") (pintype "bidirectional"))
    )
    (net (code "22") (name "Net-(C1-P$1)") (class "Default")
      (node (ref "C1") (pin "1") (pinfunction "P$1_1") (pintype "passive"))
      (node (ref "DA1") (pin "10") (pinfunction "IN+_10") (pintype "bidirectional"))
      (node (ref "R36") (pin "1") (pinfunction "1_1") (pintype "passive"))
    )
    (net (code "23") (name "Net-(C1-P$2)") (class "Default")
      (node (ref "C1") (pin "2") (pinfunction "P$2_2") (pintype "passive"))
      (node (ref "DA1") (pin "9") (pinfunction "IN-_9") (pintype "bidirectional"))
      (node (ref "R37") (pin "1") (pinfunction "1_1") (pintype "passive"))
    )
    (net (code "24") (name "Net-(C3-P$1)") (class "Default")
      (node (ref "C3") (pin "1") (pinfunction "P$1_1") (pintype "passive"))
      (node (ref "R9") (pin "2") (pinfunction "2_2") (pintype "passive"))
      (node (ref "S1") (pin "3") (pinfunction "3_3") (pintype "passive"))
      (node (ref "S1") (pin "4") (pinfunction "4_4") (pintype "passive"))
    )
    (net (code "25") (name "Net-(C6-P$1)") (class "Default")
      (node (ref "C6") (pin "1") (pinfunction "P$1_1") (pintype "passive"))
      (node (ref "R14") (pin "2") (pinfunction "2_2") (pintype "passive"))
      (node (ref "S2") (pin "3") (pinfunction "3_3") (pintype "passive"))
      (node (ref "S2") (pin "4") (pinfunction "4_4") (pintype "passive"))
    )
    (net (code "26") (name "Net-(C11-P$2)") (class "Default")
      (node (ref "C11") (pin "2") (pinfunction "P$2_2") (pintype "passive"))
      (node (ref "FB2") (pin "1") (pinfunction "1_1") (pintype "bidirectional"))
      (node (ref "U3") (pin "9") (pinfunction "VDDA_9") (pintype "bidirectional"))
    )
    (net (code "27") (name "Net-(C16-P$2)") (class "Default")
      (node (ref "C16") (pin "2") (pinfunction "P$2_2") (pintype "passive"))
      (node (ref "Q4") (pin "3") (pinfunction "C_3") (pintype "passive"))
      (node (ref "R35") (pin "2") (pinfunction "2_2") (pintype "passive"))
    )
    (net (code "28") (name "Net-(C17-P$1)") (class "Default")
      (node (ref "C17") (pin "1") (pinfunction "P$1_1") (pintype "passive"))
      (node (ref "R11") (pin "2") (pinfunction "2_2") (pintype "passive"))
      (node (ref "R12") (pin "2") (pinfunction "2_2") (pintype "passive"))
    )
    (net (code "29") (name "Net-(C21-P$1)") (class "Default")
      (node (ref "C21") (pin "1") (pinfunction "P$1_1") (pintype "passive"))
      (node (ref "LCD1") (pin "1") (pinfunction "C2+_1") (pintype "bidirectional"))
    )
    (net (code "30") (name "Net-(C21-P$2)") (class "Default")
      (node (ref "C21") (pin "2") (pinfunction "P$2_2") (pintype "passive"))
      (node (ref "LCD1") (pin "2") (pinfunction "C2-_2") (pintype "bidirectional"))
    )
    (net (code "31") (name "Net-(C22-P$1)") (class "Default")
      (node (ref "C22") (pin "1") (pinfunction "P$1_1") (pintype "passive"))
      (node (ref "LCD1") (pin "3") (pinfunction "C1+_3") (pintype "bidirectional"))
    )
    (net (code "32") (name "Net-(C22-P$2)") (class "Default")
      (node (ref "C22") (pin "2") (pinfunction "P$2_2") (pintype "passive"))
      (node (ref "LCD1") (pin "4") (pinfunction "C1-_4") (pintype "bidirectional"))
    )
    (net (code "33") (name "Net-(C25-P$1)") (class "Default")
      (node (ref "C25") (pin "1") (pinfunction "P$1_1") (pintype "passive"))
      (node (ref "LCD1") (pin "13") (pinfunction "VCOMH_13") (pintype "power_in"))
    )
    (net (code "34") (name "Net-(C26-P$1)") (class "Default")
      (node (ref "C26") (pin "1") (pinfunction "P$1_1") (pintype "passive"))
      (node (ref "LCD1") (pin "14") (pinfunction "VCC_14") (pintype "power_in"))
    )
    (net (code "35") (name "Net-(C27-P$1)") (class "Default")
      (node (ref "C27") (pin "1") (pinfunction "P$1_1") (pintype "passive"))
      (node (ref "D9") (pin "C") (pinfunction "C_C") (pintype "passive"))
      (node (ref "PAD1") (pin "TP") (pinfunction "TP_TP") (pintype "input"))
      (node (ref "PAD2") (pin "TP") (pinfunction "TP_TP") (pintype "input"))
      (node (ref "PAD3") (pin "TP") (pinfunction "TP_TP") (pintype "input"))
      (node (ref "PAD4") (pin "TP") (pinfunction "TP_TP") (pintype "input"))
      (node (ref "Q3") (pin "5") (pinfunction "D_5") (pintype "passive"))
      (node (ref "Q3") (pin "6") (pinfunction "D_6") (pintype "passive"))
      (node (ref "Q3") (pin "7") (pinfunction "D_7") (pintype "passive"))
      (node (ref "Q3") (pin "8") (pinfunction "D_8") (pintype "passive"))
      (node (ref "Q3") (pin "9") (pinfunction "D_9") (pintype "passive"))
      (node (ref "R13") (pin "1") (pinfunction "1_1") (pintype "passive"))
      (node (ref "R42") (pin "2") (pinfunction "2_2") (pintype "passive"))
      (node (ref "T1") (pin "1A") (pinfunction "P$1_1A") (pintype "bidirectional"))
      (node (ref "T1") (pin "1B") (pinfunction "P$1_1B") (pintype "bidirectional"))
    )
    (net (code "36") (name "Net-(C29-P$1)") (class "Default")
      (node (ref "C29") (pin "1") (pinfunction "P$1_1") (pintype "passive"))
      (node (ref "U4") (pin "1") (pinfunction "BS_1") (pintype "bidirectional"))
    )
    (net (code "37") (name "Net-(C29-P$2)") (class "Default")
      (node (ref "C29") (pin "2") (pinfunction "P$2_2") (pintype "passive"))
      (node (ref "D7") (pin "C") (pinfunction "C_C") (pintype "passive"))
      (node (ref "L1") (pin "1") (pinfunction "1_1") (pintype "passive"))
      (node (ref "U4") (pin "6") (pinfunction "SW_6") (pintype "bidirectional"))
    )
    (net (code "38") (name "Net-(C32-P$2)") (class "Default")
      (node (ref "C32") (pin "2") (pinfunction "P$2_2") (pintype "passive"))
      (node (ref "R1") (pin "2") (pinfunction "2_2") (pintype "passive"))
      (node (ref "R2") (pin "2") (pinfunction "2_2") (pintype "passive"))
      (node (ref "U4") (pin "3") (pinfunction "FB_3") (pintype "bidirectional"))
    )
    (net (code "39") (name "Net-(D3-PadC)") (class "Default")
      (node (ref "D3") (pin "C") (pinfunction "C_C") (pintype "passive"))
      (node (ref "Q2") (pin "1") (pinfunction "S_1") (pintype "passive"))
      (node (ref "Q2") (pin "2") (pinfunction "S_2") (pintype "passive"))
      (node (ref "Q2") (pin "3") (pinfunction "S_3") (pintype "passive"))
      (node (ref "Q3") (pin "1") (pinfunction "S_1") (pintype "passive"))
      (node (ref "Q3") (pin "2") (pinfunction "S_2") (pintype "passive"))
      (node (ref "Q3") (pin "3") (pinfunction "S_3") (pintype "passive"))
    )
    (net (code "40") (name "Net-(LCD1-IREF)") (class "Default")
      (node (ref "LCD1") (pin "12") (pinfunction "IREF_12") (pintype "bidirectional"))
      (node (ref "R17") (pin "2") (pinfunction "2_2") (pintype "passive"))
    )
    (net (code "41") (name "Net-(Q2-G)") (class "Default")
      (node (ref "D3") (pin "A") (pinfunction "A_A") (pintype "passive"))
      (node (ref "Q2") (pin "4") (pinfunction "G_4") (pintype "passive"))
      (node (ref "Q3") (pin "4") (pinfunction "G_4") (pintype "passive"))
      (node (ref "R10") (pin "2") (pinfunction "2_2") (pintype "passive"))
      (node (ref "R35") (pin "1") (pinfunction "1_1") (pintype "passive"))
    )
    (net (code "42") (name "Net-(Q4-B)") (class "Default")
      (node (ref "Q4") (pin "1") (pinfunction "B_1") (pintype "passive"))
      (node (ref "R11") (pin "1") (pinfunction "1_1") (pintype "passive"))
    )
    (net (code "43") (name "Net-(R7-Pad2)") (class "Default")
      (node (ref "R7") (pin "2") (pinfunction "2_2") (pintype "passive"))
      (node (ref "S3") (pin "1") (pinfunction "1_1") (pintype "passive"))
      (node (ref "S3") (pin "2") (pinfunction "2_2") (pintype "passive"))
    )
    (net (code "44") (name "Net-(U1-VBUS)") (class "Default")
      (node (ref "FB5") (pin "1") (pinfunction "1_1") (pintype "bidirectional"))
      (node (ref "U1") (pin "2") (pinfunction "VBUS_2") (pintype "bidirectional"))
    )
    (net (code "45") (name "Net-(U4-EN)") (class "Default")
      (node (ref "R20") (pin "1") (pinfunction "1_1") (pintype "passive"))
      (node (ref "U4") (pin "4") (pinfunction "EN_4") (pintype "bidirectional"))
    )
    (net (code "46") (name "Net-(U5-VOUT)") (class "Default")
      (node (ref "R41") (pin "2") (pinfunction "2_2") (pintype "passive"))
      (node (ref "U5") (pin "2") (pinfunction "VOUT_2") (pintype "input"))
    )
    (net (code "47") (name "Net-(VD1-P$4)") (class "Default")
      (node (ref "R27") (pin "1") (pinfunction "1_1") (pintype "passive"))
      (node (ref "R4") (pin "1") (pinfunction "1_1") (pintype "passive"))
      (node (ref "R5") (pin "1") (pinfunction "1_1") (pintype "passive"))
      (node (ref "VD1") (pin "4") (pinfunction "P$4_4") (pintype "bidirectional"))
    )
    (net (code "48") (name "Net-(VD1-P$6)") (class "Default")
      (node (ref "R28") (pin "1") (pinfunction "1_1") (pintype "passive"))
      (node (ref "R6") (pin "1") (pinfunction "1_1") (pintype "passive"))
      (node (ref "VD1") (pin "6") (pinfunction "P$6_6") (pintype "bidirectional"))
    )
    (net (code "49") (name "OSC_IN") (class "Default")
      (node (ref "C8") (pin "2") (pinfunction "P$2_2") (pintype "passive"))
      (node (ref "U3") (pin "5") (pinfunction "PF0/OSC_IN_5") (pintype "bidirectional"))
      (node (ref "ZO1") (pin "3") (pinfunction "P$2_3") (pintype "bidirectional"))
    )
    (net (code "50") (name "OSC_OUT") (class "Default")
      (node (ref "C9") (pin "2") (pinfunction "P$2_2") (pintype "passive"))
      (node (ref "U3") (pin "6") (pinfunction "PF1/OSC_OUT\\_6") (pintype "bidirectional"))
      (node (ref "ZO1") (pin "1") (pinfunction "P$1_1") (pintype "bidirectional"))
    )
    (net (code "51") (name "PA0") (class "Default")
      (node (ref "U3") (pin "10") (pinfunction "PA0_10") (pintype "bidirectional"))
    )
    (net (code "52") (name "PA1") (class "Default")
      (node (ref "U3") (pin "11") (pinfunction "PA1_11") (pintype "bidirectional"))
    )
    (net (code "53") (name "PA2{slash}ADC2") (class "Default")
      (node (ref "R41") (pin "1") (pinfunction "1_1") (pintype "passive"))
      (node (ref "U3") (pin "12") (pinfunction "PA2_12") (pintype "bidirectional"))
    )
    (net (code "54") (name "PA3{slash}T2C4") (class "Default")
      (node (ref "C17") (pin "2") (pinfunction "P$2_2") (pintype "passive"))
      (node (ref "U3") (pin "13") (pinfunction "PA3_13") (pintype "bidirectional"))
    )
    (net (code "55") (name "PA4") (class "Default")
      (node (ref "U3") (pin "14") (pinfunction "PA4_14") (pintype "bidirectional"))
    )
    (net (code "56") (name "PA5") (class "Default")
      (node (ref "U3") (pin "15") (pinfunction "PA5_15") (pintype "bidirectional"))
    )
    (net (code "57") (name "PA6") (class "Default")
      (node (ref "U3") (pin "16") (pinfunction "PA6_16") (pintype "bidirectional"))
    )
    (net (code "58") (name "PA7{slash}T1CH1N{slash}T3C2") (class "Default")
      (node (ref "BUZ1") (pin "+") (pinfunction "LEAD+_+") (pintype "passive"))
      (node (ref "U3") (pin "17") (pinfunction "PA7_17") (pintype "bidirectional"))
    )
    (net (code "59") (name "PA8{slash}T1C1") (class "Default")
      (node (ref "U3") (pin "29") (pinfunction "PA8_29") (pintype "bidirectional"))
    )
    (net (code "60") (name "PA9{slash}T1C2") (class "Default")
      (node (ref "U3") (pin "30") (pinfunction "PA9_30") (pintype "bidirectional"))
    )
    (net (code "61") (name "PA10{slash}IT_ACCEL_1") (class "Default")
      (node (ref "U3") (pin "31") (pinfunction "PA10_31") (pintype "bidirectional"))
      (node (ref "U8") (pin "11") (pinfunction "INT1_11") (pintype "bidirectional"))
    )
    (net (code "62") (name "PA11{slash}USB_DM") (class "Default")
      (node (ref "R6") (pin "2") (pinfunction "2_2") (pintype "passive"))
      (node (ref "U3") (pin "32") (pinfunction "PA11_32") (pintype "bidirectional"))
    )
    (net (code "63") (name "PA12{slash}USB_DP") (class "Default")
      (node (ref "R5") (pin "2") (pinfunction "2_2") (pintype "passive"))
      (node (ref "U3") (pin "33") (pinfunction "PA12_33") (pintype "bidirectional"))
    )
    (net (code "64") (name "PA13{slash}SWDIO") (class "Default")
      (node (ref "R27") (pin "2") (pinfunction "2_2") (pintype "passive"))
      (node (ref "U3") (pin "34") (pinfunction "PA13_34") (pintype "bidirectional"))
    )
    (net (code "65") (name "PA14{slash}SWCLK") (class "Default")
      (node (ref "R28") (pin "2") (pinfunction "2_2") (pintype "passive"))
      (node (ref "U3") (pin "37") (pinfunction "PA14_37") (pintype "bidirectional"))
    )
    (net (code "66") (name "PA15") (class "Default")
      (node (ref "U3") (pin "38") (pinfunction "PA15_38") (pintype "bidirectional"))
    )
    (net (code "67") (name "PB0{slash}ADC8") (class "Default")
      (node (ref "R45") (pin "1") (pinfunction "1_1") (pintype "passive"))
      (node (ref "U3") (pin "18") (pinfunction "PB0_18") (pintype "bidirectional"))
    )
    (net (code "68") (name "PB1{slash}IT_FUSB302") (class "Default")
      (node (ref "R16") (pin "2") (pinfunction "2_2") (pintype "passive"))
      (node (ref "U1") (pin "5") (pinfunction "~{INT}_5") (pintype "bidirectional"))
      (node (ref "U3") (pin "19") (pinfunction "PB1_19") (pintype "bidirectional"))
    )
    (net (code "69") (name "PB3{slash}IT_ACCEL_2") (class "Default")
      (node (ref "TP5") (pin "P$1") (pinfunction "1_P$1") (pintype "bidirectional"))
      (node (ref "U3") (pin "39") (pinfunction "PB3_39") (pintype "bidirectional"))
      (node (ref "U8") (pin "9") (pinfunction "INT2_9") (pintype "bidirectional"))
    )
    (net (code "70") (name "PB4") (class "Default")
      (node (ref "U3") (pin "40") (pinfunction "PB4_40") (pintype "bidirectional"))
    )
    (net (code "71") (name "PB5") (class "Default")
      (node (ref "U3") (pin "41") (pinfunction "PB5_41") (pintype "bidirectional"))
    )
    (net (code "72") (name "PB6{slash}SCL1") (class "Default")
      (node (ref "LCD1") (pin "10") (pinfunction "SCL_10") (pintype "bidirectional"))
      (node (ref "R19") (pin "1") (pinfunction "1_1") (pintype "passive"))
      (node (ref "U3") (pin "42") (pinfunction "PB6_42") (pintype "bidirectional"))
    )
    (net (code "73") (name "PB7{slash}SDA1") (class "Default")
      (node (ref "LCD1") (pin "11") (pinfunction "SDA_11") (pintype "bidirectional"))
      (node (ref "R18") (pin "1") (pinfunction "1_1") (pintype "passive"))
      (node (ref "U3") (pin "43") (pinfunction "PB7_43") (pintype "bidirectional"))
    )
    (net (code "74") (name "PB8&BOOT0_S3") (class "Default")
      (node (ref "R7") (pin "1") (pinfunction "1_1") (pintype "passive"))
      (node (ref "R8") (pin "1") (pinfunction "1_1") (pintype "passive"))
      (node (ref "U3") (pin "44") (pinfunction "BOOT0_44") (pintype "bidirectional"))
      (node (ref "U3") (pin "45") (pinfunction "PB8_45") (pintype "bidirectional"))
    )
    (net (code "75") (name "PB9{slash}S1") (class "Default")
      (node (ref "R9") (pin "1") (pinfunction "1_1") (pintype "passive"))
      (node (ref "U3") (pin "46") (pinfunction "PB9_46") (pintype "bidirectional"))
    )
    (net (code "76") (name "PB10{slash}SCL2") (class "Default")
      (node (ref "DA1") (pin "5") (pinfunction "SCL_5") (pintype "bidirectional"))
      (node (ref "R3") (pin "2") (pinfunction "2_2") (pintype "passive"))
      (node (ref "U1") (pin "6") (pinfunction "SCL_6") (pintype "bidirectional"))
      (node (ref "U3") (pin "21") (pinfunction "PB10_21") (pintype "bidirectional"))
      (node (ref "U8") (pin "4") (pinfunction "SCL/SPC_4") (pintype "bidirectional"))
    )
    (net (code "77") (name "PB11{slash}SDA2") (class "Default")
      (node (ref "DA1") (pin "4") (pinfunction "SDA_4") (pintype "bidirectional"))
      (node (ref "R25") (pin "2") (pinfunction "2_2") (pintype "passive"))
      (node (ref "U1") (pin "7") (pinfunction "SDA_7") (pintype "bidirectional"))
      (node (ref "U3") (pin "22") (pinfunction "PB11_22") (pintype "bidirectional"))
      (node (ref "U8") (pin "6") (pinfunction "SDA/SDI_6") (pintype "bidirectional"))
    )
    (net (code "78") (name "PB12") (class "Default")
      (node (ref "U3") (pin "25") (pinfunction "PB12_25") (pintype "bidirectional"))
    )
    (net (code "79") (name "PB13{slash}IT_INA226") (class "Default")
      (node (ref "DA1") (pin "3") (pinfunction "ALERT_3") (pintype "bidirectional"))
      (node (ref "R38") (pin "2") (pinfunction "2_2") (pintype "passive"))
      (node (ref "U3") (pin "26") (pinfunction "PB13_26") (pintype "bidirectional"))
    )
    (net (code "80") (name "PB14{slash}MISO2") (class "Default")
      (node (ref "U3") (pin "27") (pinfunction "PB14_27") (pintype "bidirectional"))
    )
    (net (code "81") (name "PB15{slash}S2") (class "Default")
      (node (ref "R14") (pin "1") (pinfunction "1_1") (pintype "passive"))
      (node (ref "U3") (pin "28") (pinfunction "PB15_28") (pintype "bidirectional"))
    )
    (net (code "82") (name "PC13") (class "Default")
      (node (ref "U3") (pin "2") (pinfunction "PC13_2") (pintype "bidirectional"))
    )
    (net (code "83") (name "PC14{slash}OSC32_IN") (class "Default")
      (node (ref "U3") (pin "3") (pinfunction "PC14/OSC32_IN_3") (pintype "bidirectional"))
    )
    (net (code "84") (name "PC15{slash}OSC32_OUT") (class "Default")
      (node (ref "U3") (pin "4") (pinfunction "PC15/OSC32_OUT_4") (pintype "bidirectional"))
    )
    (net (code "85") (name "PGND") (class "Default")
      (node (ref "CP1") (pin "1A") (pinfunction "P$1_1A") (pintype "bidirectional"))
      (node (ref "CP1") (pin "1B") (pinfunction "P$1_1B") (pintype "bidirectional"))
      (node (ref "PAD10") (pin "TP") (pinfunction "TP_TP") (pintype "input"))
      (node (ref "PAD11") (pin "TP") (pinfunction "TP_TP") (pintype "input"))
      (node (ref "PAD12") (pin "TP") (pinfunction "TP_TP") (pintype "input"))
      (node (ref "PAD9") (pin "TP") (pinfunction "TP_TP") (pintype "input"))
      (node (ref "TP1") (pin "P$1") (pinfunction "P$1_P$1") (pintype "bidirectional"))
    )
    (net (code "86") (name "SAO{slash}SDO{slash}ADDR") (class "Default")
      (node (ref "U8") (pin "7") (pinfunction "SA0/SDO_7") (pintype "bidirectional"))
    )
    (net (code "87") (name "VBUS-C") (class "Default")
      (node (ref "D1") (pin "A") (pinfunction "A_A") (pintype "passive"))
      (node (ref "FB5") (pin "2") (pinfunction "2_2") (pintype "bidirectional"))
      (node (ref "Q2") (pin "5") (pinfunction "D_5") (pintype "passive"))
      (node (ref "Q2") (pin "6") (pinfunction "D_6") (pintype "passive"))
      (node (ref "Q2") (pin "7") (pinfunction "D_7") (pintype "passive"))
      (node (ref "Q2") (pin "8") (pinfunction "D_8") (pintype "passive"))
      (node (ref "Q2") (pin "9") (pinfunction "D_9") (pintype "passive"))
      (node (ref "R10") (pin "1") (pinfunction "1_1") (pintype "passive"))
      (node (ref "R24") (pin "1") (pinfunction "1_1") (pintype "passive"))
      (node (ref "R37") (pin "2") (pinfunction "2_2") (pintype "passive"))
    )
    (net (code "88") (name "unconnected-(J3-SBU1-PadA8)") (class "Default")
      (node (ref "J3") (pin "A8") (pinfunction "SBU1_A8") (pintype "bidirectional"))
    )
    (net (code "89") (name "unconnected-(J3-SBU2-PadB8)") (class "Default")
      (node (ref "J3") (pin "B8") (pinfunction "SBU2_B8") (pintype "bidirectional"))
    )
    (net (code "90") (name "unconnected-(U1-VCONN_01-Pad12)") (class "Default")
      (node (ref "U1") (pin "12") (pinfunction "VCONN_01_12") (pintype "bidirectional"))
    )
    (net (code "91") (name "unconnected-(U1-VCONN_02-Pad13)") (class "Default")
      (node (ref "U1") (pin "13") (pinfunction "VCONN_02_13") (pintype "bidirectional"))
    )
    (net (code "92") (name "unconnected-(VD1-P$5-Pad5)") (class "Default")
      (node (ref "VD1") (pin "5") (pinfunction "P$5_5") (pintype "bidirectional"))
    )
  )
)
